# soldering_iron_2.net
KiCad netlist of a schematic drawn in Altium Designer
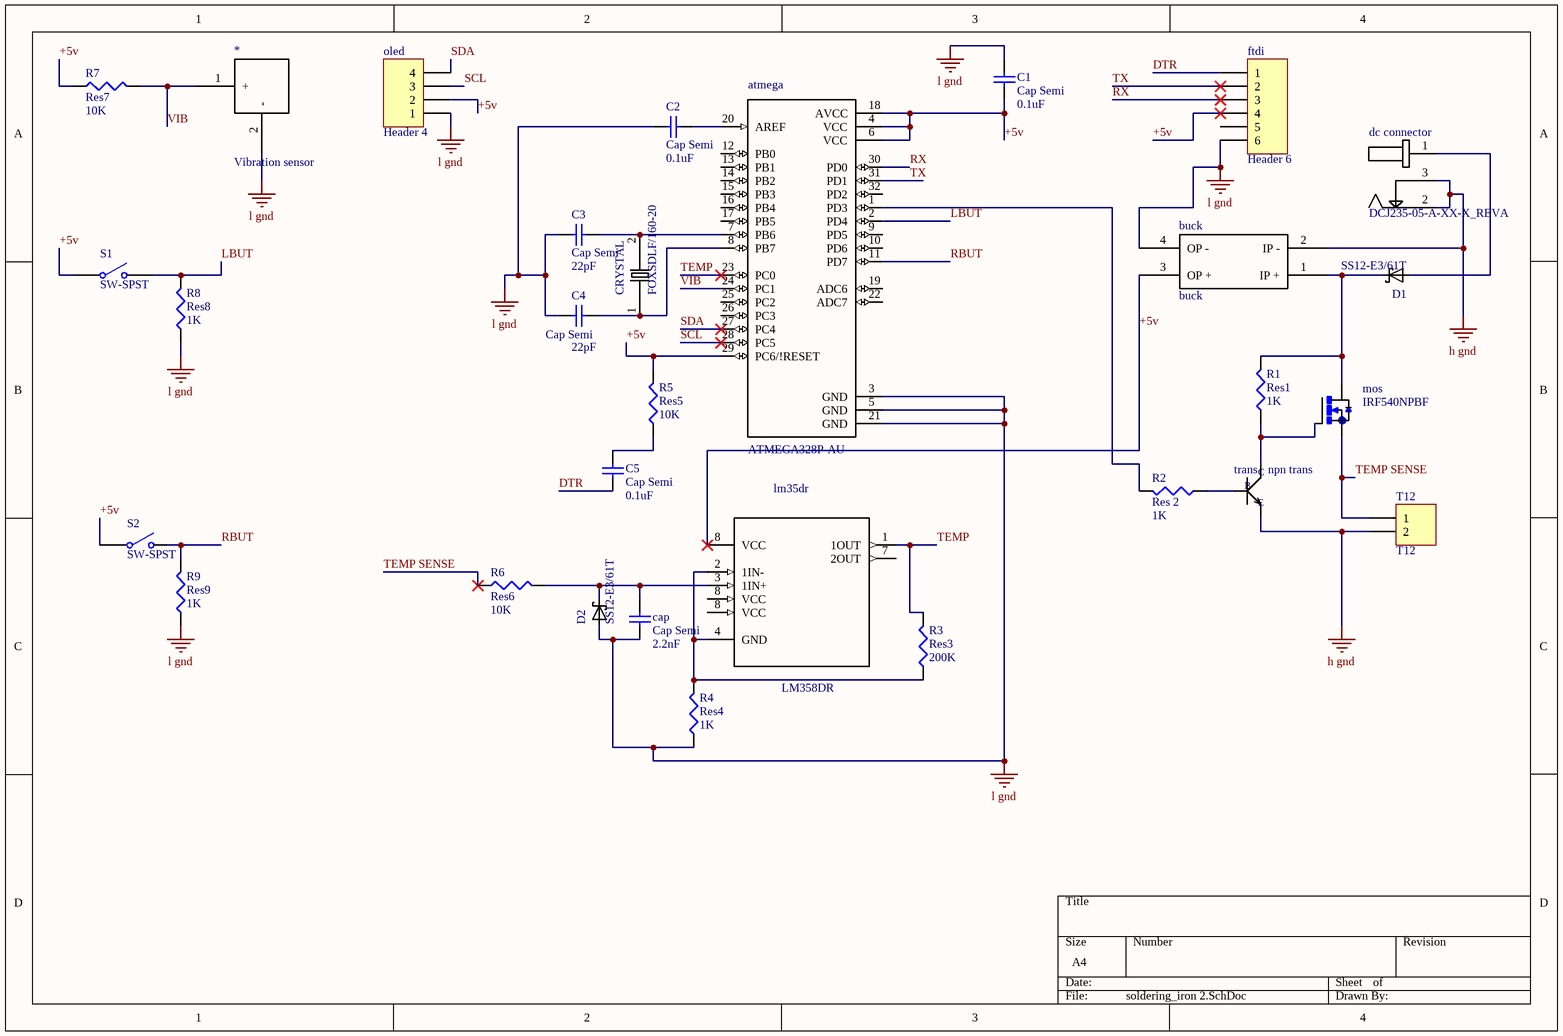
[diagram p0: soldering_iron 2.SchDoc]

(export (version "E")
  (design (tool "Eeschema 10.0.6"))
  (components
    (comp (ref "*")
      (value "Vibration sensor")
      (footprint "vibration sensor:PCBComponent_1")
      (libsource (lib "vibration sensor") (part "Component_1"))
    )
    (comp (ref "atmega")
      (value "ATMEGA328P-AU")
      (footprint "*QFP80P900X900X120-32N")
      (description "Microcontroller Mcu, 8 Bit, Atmega, 20mhz, Tqfp-32")
      (fields (field (name "DIGI-KEY_PART_NUMBER") "ATMEGA328P-AU-ND") (field (name "MF") "Microchip"))
      (libsource (lib "ATMEGA328P-AU") (part "ATMEGA328P-AU"))
    )
    (comp (ref "buck") (value "buck") (footprint "buck:buck") (libsource (lib "Schlib1") (part "buck")))
    (comp (ref "C1")
      (value "Cap Semi")
      (footprint "C1206")
      (description "Capacitor (Semiconductor SIM Model)")
      (fields (field (name "ALTIUM_VALUE") "0.1uF") (field (name "PUBLISHER") "Altium Limited"))
      (libsource (lib "Miscellaneous Devices") (part "Cap Semi"))
    )
    (comp (ref "C2")
      (value "Cap Semi")
      (footprint "C1206")
      (description "Capacitor (Semiconductor SIM Model)")
      (fields (field (name "ALTIUM_VALUE") "0.1uF") (field (name "PUBLISHER") "Altium Limited"))
      (libsource (lib "Miscellaneous Devices") (part "Cap Semi"))
    )
    (comp (ref "C3")
      (value "Cap Semi")
      (footprint "C1206")
      (description "Capacitor (Semiconductor SIM Model)")
      (fields (field (name "ALTIUM_VALUE") "22pF") (field (name "PUBLISHER") "Altium Limited"))
      (libsource (lib "Miscellaneous Devices") (part "Cap Semi"))
    )
    (comp (ref "C4")
      (value "Cap Semi")
      (footprint "C1206")
      (description "Capacitor (Semiconductor SIM Model)")
      (fields (field (name "ALTIUM_VALUE") "22pF") (field (name "PUBLISHER") "Altium Limited"))
      (libsource (lib "Miscellaneous Devices") (part "Cap Semi"))
    )
    (comp (ref "C5")
      (value "Cap Semi")
      (footprint "C1206")
      (description "Capacitor (Semiconductor SIM Model)")
      (fields (field (name "ALTIUM_VALUE") "0.1uF") (field (name "PUBLISHER") "Altium Limited"))
      (libsource (lib "Miscellaneous Devices") (part "Cap Semi"))
    )
    (comp (ref "cap")
      (value "Cap Semi")
      (footprint "C1206")
      (description "Capacitor (Semiconductor SIM Model)")
      (fields (field (name "ALTIUM_VALUE") "2.2nF") (field (name "PUBLISHER") "Altium Limited"))
      (libsource (lib "Miscellaneous Devices") (part "Cap Semi"))
    )
    (comp (ref "CRYSTAL")
      (value "FOXSDLF/160-20")
      (footprint "*XTAL_FOXSDLF/160-20")
      (description "Crystal 16MHz Â±30ppm _Tol_ Â±50ppm _Stability_ 20pF FUND 40Ohm 2-Pin HC-49/SDLF SMD T/R")
      (fields (field (name "MP") "FOXSDLF/160-20/TR") (field (name "MF") "Fox Electronics"))
      (libsource (lib "FOXSDLF_160-20") (part "FOXSDLF/160-20"))
    )
    (comp (ref "D1")
      (value "SS12-E3/61T")
      (footprint "*DO214AC_SS12-E3/61T(Primary)")
      (description "SS12 Series 20 V 1 A Surface Mount Schottky Barrier Rectifier - DO-214AC _SMA_")
      (fields (field (name "MF") "Vishay Semiconductor"))
      (libsource (lib "SS12-E3_61T") (part "SS12-E3/61T"))
    )
    (comp (ref "D2")
      (value "SS12-E3/61T")
      (footprint "*DO214AC_SS12-E3/61T(Primary)")
      (description "SS12 Series 20 V 1 A Surface Mount Schottky Barrier Rectifier - DO-214AC _SMA_")
      (fields (field (name "MF") "Vishay Semiconductor"))
      (libsource (lib "SS12-E3_61T") (part "SS12-E3/61T"))
    )
    (comp (ref "dc connector")
      (value "DCJ235-05-A-XX-X_REVA")
      (footprint "*GCT_DCJ235-05-A-XX-X_REVA")
      (description "Dc Power Jack, 5a, 20vdc, Black")
      (fields (field (name "MF") "Global Connector Technology") (field (name "MP") "DCJ235-05-A-K1-A"))
      (libsource (lib "DCJ235-05-A-XX-X_REVA") (part "DCJ235-05-A-XX-X_REVA"))
    )
    (comp (ref "ftdi")
      (value "Header 6")
      (footprint "HDR1X6")
      (description "Header, 6-Pin")
      (fields (field (name "PUBLISHER") "Altium Limited"))
      (libsource (lib "Miscellaneous Connectors") (part "Header 6"))
    )
    (comp (ref "lm35dr")
      (value "LM358DR")
      (footprint "*SOIC127P600X175-8N")
      (description "Dual Operational Amplifiers 8-SOIC 0 to 70")
      (fields (field (name "MF") "Texas Instruments"))
      (libsource (lib "LM358DR") (part "LM358DR"))
    )
    (comp (ref "mos")
      (value "IRF540NPBF")
      (footprint "*D2PACK")
      (description "Single N-Channel 100 V 44 mOhm 71 nC HEXFETÂ® Power Mosfet - TO-220-3")
      (fields (field (name "DIGI-KEY_PART_NUMBER") "IRF540NPBF-ND") (field (name "MF") "Infineon"))
      (libsource (lib "IRF540NPBF") (part "IRF540NPBF"))
    )
    (comp (ref "oled")
      (value "Header 4")
      (footprint "HDR1X4")
      (description "Header, 4-Pin")
      (fields (field (name "PUBLISHER") "Altium Limited"))
      (libsource (lib "Miscellaneous Connectors") (part "Header 4"))
    )
    (comp (ref "R1")
      (value "Res1")
      (footprint "J1-0603")
      (description "Resistor")
      (fields (field (name "ALTIUM_VALUE") "1K") (field (name "PUBLISHER") "Altium Limited"))
      (libsource (lib "Miscellaneous Devices") (part "Res3"))
    )
    (comp (ref "R2")
      (value "Res 2")
      (footprint "J1-0603")
      (description "Resistor")
      (fields (field (name "ALTIUM_VALUE") "1K") (field (name "PUBLISHER") "Altium Limited"))
      (libsource (lib "Miscellaneous Devices") (part "Res3"))
    )
    (comp (ref "R3")
      (value "Res3")
      (footprint "J1-0603")
      (description "Resistor")
      (fields (field (name "ALTIUM_VALUE") "200K") (field (name "PUBLISHER") "Altium Limited"))
      (libsource (lib "Miscellaneous Devices") (part "Res3"))
    )
    (comp (ref "R4")
      (value "Res4")
      (footprint "J1-0603")
      (description "Resistor")
      (fields (field (name "ALTIUM_VALUE") "1K") (field (name "PUBLISHER") "Altium Limited"))
      (libsource (lib "Miscellaneous Devices") (part "Res3"))
    )
    (comp (ref "R5")
      (value "Res5")
      (footprint "J1-0603")
      (description "Resistor")
      (fields (field (name "ALTIUM_VALUE") "10K") (field (name "PUBLISHER") "Altium Limited"))
      (libsource (lib "Miscellaneous Devices") (part "Res3"))
    )
    (comp (ref "R6")
      (value "Res6")
      (footprint "J1-0603")
      (description "Resistor")
      (fields (field (name "ALTIUM_VALUE") "10K") (field (name "PUBLISHER") "Altium Limited"))
      (libsource (lib "Miscellaneous Devices") (part "Res3"))
    )
    (comp (ref "R7")
      (value "Res7")
      (footprint "J1-0603")
      (description "Resistor")
      (fields (field (name "ALTIUM_VALUE") "10K") (field (name "PUBLISHER") "Altium Limited"))
      (libsource (lib "Miscellaneous Devices") (part "Res3"))
    )
    (comp (ref "R8")
      (value "Res8")
      (footprint "J1-0603")
      (description "Resistor")
      (fields (field (name "ALTIUM_VALUE") "1K") (field (name "PUBLISHER") "Altium Limited"))
      (libsource (lib "Miscellaneous Devices") (part "Res3"))
    )
    (comp (ref "R9")
      (value "Res9")
      (footprint "J1-0603")
      (description "Resistor")
      (fields (field (name "ALTIUM_VALUE") "1K") (field (name "PUBLISHER") "Altium Limited"))
      (libsource (lib "Miscellaneous Devices") (part "Res3"))
    )
    (comp (ref "S1")
      (value "SW-SPST")
      (footprint "SPST-2")
      (description "Single-Pole, Single-Throw Switch")
      (fields (field (name "PUBLISHER") "Altium Limited"))
      (libsource (lib "Miscellaneous Devices") (part "SW-SPST"))
    )
    (comp (ref "S2")
      (value "SW-SPST")
      (footprint "SPST-2")
      (description "Single-Pole, Single-Throw Switch")
      (fields (field (name "PUBLISHER") "Altium Limited"))
      (libsource (lib "Miscellaneous Devices") (part "SW-SPST"))
    )
    (comp (ref "T12")
      (value "T12")
      (footprint "HDR1X2")
      (description "Header, 2-Pin")
      (fields (field (name "PUBLISHER") "Altium Limited"))
      (libsource (lib "Miscellaneous Connectors") (part "Header 2"))
    )
    (comp (ref "trans")
      (value "npn trans")
      (footprint "*SOT-23")
      (description "SMD Transistors NPN 25V-500mA")
      (fields (field (name "MP") "S9013") (field (name "MF") "JCET"))
      (libsource (lib "SMD-TRANSISTORS-NPN-25V-500MA-S9013_SOT-23_") (part "SMD-TRANSISTORS-NPN-25V-500MA-S9013(SOT-23)"))
    )
  )
  (nets
    (net (code "1") (name "/+5v") (class "Default")
      (node (ref "C1") (pin "1") (pinfunction "1_1") (pintype "passive"))
      (node (ref "R5") (pin "2") (pinfunction "2_2") (pintype "passive"))
      (node (ref "R7") (pin "1") (pinfunction "1_1") (pintype "passive"))
      (node (ref "S1") (pin "1") (pinfunction "COMMON_1") (pintype "passive"))
      (node (ref "S2") (pin "1") (pinfunction "COMMON_1") (pintype "passive"))
      (node (ref "atmega") (pin "18") (pinfunction "AVCC_18") (pintype "power_in"))
      (node (ref "atmega") (pin "29") (pinfunction "PC6/!RESET_29") (pintype "bidirectional"))
      (node (ref "atmega") (pin "4") (pinfunction "VCC_4") (pintype "power_in"))
      (node (ref "atmega") (pin "6") (pinfunction "VCC_6") (pintype "power_in"))
      (node (ref "buck") (pin "3") (pinfunction "OP_+_3") (pintype "passive"))
      (node (ref "ftdi") (pin "4") (pinfunction "4_4") (pintype "passive"))
      (node (ref "lm35dr") (pin "8") (pinfunction "VCC_8") (pintype "power_in"))
      (node (ref "oled") (pin "2") (pinfunction "2_2") (pintype "passive"))
    )
    (net (code "2") (name "/DTR") (class "Default")
      (node (ref "C5") (pin "1") (pinfunction "1_1") (pintype "passive"))
      (node (ref "ftdi") (pin "1") (pinfunction "1_1") (pintype "passive"))
    )
    (net (code "3") (name "/LBUT") (class "Default")
      (node (ref "R8") (pin "2") (pinfunction "2_2") (pintype "passive"))
      (node (ref "S1") (pin "2") (pinfunction "NO_2") (pintype "passive"))
      (node (ref "atmega") (pin "2") (pinfunction "PD4_2") (pintype "bidirectional"))
    )
    (net (code "4") (name "/RBUT") (class "Default")
      (node (ref "R9") (pin "2") (pinfunction "2_2") (pintype "passive"))
      (node (ref "S2") (pin "2") (pinfunction "NO_2") (pintype "passive"))
      (node (ref "atmega") (pin "11") (pinfunction "PD7_11") (pintype "bidirectional"))
    )
    (net (code "5") (name "/RX") (class "Default")
      (node (ref "atmega") (pin "30") (pinfunction "PD0_30") (pintype "bidirectional"))
      (node (ref "ftdi") (pin "3") (pinfunction "3_3") (pintype "passive"))
    )
    (net (code "6") (name "/SCL") (class "Default")
      (node (ref "atmega") (pin "28") (pinfunction "PC5_28") (pintype "bidirectional"))
      (node (ref "oled") (pin "3") (pinfunction "3_3") (pintype "passive"))
    )
    (net (code "7") (name "/SDA") (class "Default")
      (node (ref "atmega") (pin "27") (pinfunction "PC4_27") (pintype "bidirectional"))
      (node (ref "oled") (pin "4") (pinfunction "4_4") (pintype "passive"))
    )
    (net (code "8") (name "/TEMP") (class "Default")
      (node (ref "R3") (pin "2") (pinfunction "2_2") (pintype "passive"))
      (node (ref "atmega") (pin "23") (pinfunction "PC0_23") (pintype "bidirectional"))
      (node (ref "lm35dr") (pin "1") (pinfunction "1OUT_1") (pintype "output"))
    )
    (net (code "9") (name "/TEMP SENSE") (class "Default")
      (node (ref "R6") (pin "1") (pinfunction "1_1") (pintype "passive"))
      (node (ref "T12") (pin "1") (pinfunction "1_1") (pintype "passive"))
      (node (ref "mos") (pin "3") (pinfunction "S_3") (pintype "passive"))
    )
    (net (code "10") (name "/TX") (class "Default")
      (node (ref "atmega") (pin "31") (pinfunction "PD1_31") (pintype "bidirectional"))
      (node (ref "ftdi") (pin "2") (pinfunction "2_2") (pintype "passive"))
    )
    (net (code "11") (name "/VIB") (class "Default")
      (node (ref "*") (pin "1") (pinfunction "+_1") (pintype "passive"))
      (node (ref "R7") (pin "2") (pinfunction "2_2") (pintype "passive"))
      (node (ref "atmega") (pin "24") (pinfunction "PC1_24") (pintype "bidirectional"))
    )
    (net (code "12") (name "Net-(C5-Pad2)") (class "Default")
      (node (ref "C5") (pin "2") (pinfunction "2_2") (pintype "passive"))
      (node (ref "R5") (pin "1") (pinfunction "1_1") (pintype "passive"))
    )
    (net (code "13") (name "Net-(D1-PadA)") (class "Default")
      (node (ref "D1") (pin "A") (pinfunction "A_A") (pintype "passive"))
      (node (ref "dc connector") (pin "1") (pinfunction "1_1") (pintype "passive"))
    )
    (net (code "14") (name "Net-(atmega-AREF)") (class "Default")
      (node (ref "C2") (pin "2") (pinfunction "2_2") (pintype "passive"))
      (node (ref "atmega") (pin "20") (pinfunction "AREF_20") (pintype "input"))
    )
    (net (code "15") (name "Net-(atmega-PB6)") (class "Default")
      (node (ref "C3") (pin "2") (pinfunction "2_2") (pintype "passive"))
      (node (ref "CRYSTAL") (pin "2") (pinfunction "2_2") (pintype "passive"))
      (node (ref "atmega") (pin "7") (pinfunction "PB6_7") (pintype "bidirectional"))
    )
    (net (code "16") (name "Net-(atmega-PB7)") (class "Default")
      (node (ref "C4") (pin "2") (pinfunction "2_2") (pintype "passive"))
      (node (ref "CRYSTAL") (pin "1") (pinfunction "1_1") (pintype "passive"))
      (node (ref "atmega") (pin "8") (pinfunction "PB7_8") (pintype "bidirectional"))
    )
    (net (code "17") (name "Net-(atmega-PD3)") (class "Default")
      (node (ref "R2") (pin "2") (pinfunction "2_2") (pintype "passive"))
      (node (ref "atmega") (pin "1") (pinfunction "PD3_1") (pintype "bidirectional"))
    )
    (net (code "18") (name "Net-(buck-IP_+)") (class "Default")
      (node (ref "D1") (pin "C") (pinfunction "C_C") (pintype "passive"))
      (node (ref "R1") (pin "2") (pinfunction "2_2") (pintype "passive"))
      (node (ref "buck") (pin "1") (pinfunction "IP_+_1") (pintype "passive"))
      (node (ref "mos") (pin "2") (pinfunction "D_2") (pintype "passive"))
    )
    (net (code "19") (name "Net-(lm35dr-1IN+)") (class "Default")
      (node (ref "D2") (pin "C") (pinfunction "C_C") (pintype "passive"))
      (node (ref "R6") (pin "2") (pinfunction "2_2") (pintype "passive"))
      (node (ref "cap") (pin "2") (pinfunction "2_2") (pintype "passive"))
      (node (ref "lm35dr") (pin "3") (pinfunction "1IN+_3") (pintype "input"))
    )
    (net (code "20") (name "Net-(lm35dr-1IN-)") (class "Default")
      (node (ref "R3") (pin "1") (pinfunction "1_1") (pintype "passive"))
      (node (ref "R4") (pin "2") (pinfunction "2_2") (pintype "passive"))
      (node (ref "lm35dr") (pin "2") (pinfunction "1IN-_2") (pintype "input"))
      (node (ref "lm35dr") (pin "4") (pinfunction "GND_4") (pintype "passive"))
    )
    (net (code "21") (name "Net-(mos-G)") (class "Default")
      (node (ref "R1") (pin "1") (pinfunction "1_1") (pintype "passive"))
      (node (ref "mos") (pin "1") (pinfunction "G_1") (pintype "passive"))
      (node (ref "trans") (pin "3") (pinfunction "C_3") (pintype "passive"))
    )
    (net (code "22") (name "Net-(trans-B)") (class "Default")
      (node (ref "R2") (pin "1") (pinfunction "1_1") (pintype "passive"))
      (node (ref "trans") (pin "1") (pinfunction "B_1") (pintype "passive"))
    )
    (net (code "23") (name "h gnd") (class "Default")
      (node (ref "T12") (pin "2") (pinfunction "2_2") (pintype "passive"))
      (node (ref "buck") (pin "2") (pinfunction "IP_-_2") (pintype "passive"))
      (node (ref "dc connector") (pin "2") (pinfunction "2_2") (pintype "passive"))
      (node (ref "dc connector") (pin "3") (pinfunction "3_3") (pintype "passive"))
      (node (ref "trans") (pin "2") (pinfunction "E_2") (pintype "passive"))
    )
    (net (code "24") (name "l gnd") (class "Default")
      (node (ref "*") (pin "2") (pinfunction "-_2") (pintype "passive"))
      (node (ref "C1") (pin "2") (pinfunction "2_2") (pintype "passive"))
      (node (ref "C2") (pin "1") (pinfunction "1_1") (pintype "passive"))
      (node (ref "C3") (pin "1") (pinfunction "1_1") (pintype "passive"))
      (node (ref "C4") (pin "1") (pinfunction "1_1") (pintype "passive"))
      (node (ref "D2") (pin "A") (pinfunction "A_A") (pintype "passive"))
      (node (ref "R4") (pin "1") (pinfunction "1_1") (pintype "passive"))
      (node (ref "R8") (pin "1") (pinfunction "1_1") (pintype "passive"))
      (node (ref "R9") (pin "1") (pinfunction "1_1") (pintype "passive"))
      (node (ref "atmega") (pin "21") (pinfunction "GND_21") (pintype "power_in"))
      (node (ref "atmega") (pin "3") (pinfunction "GND_3") (pintype "power_in"))
      (node (ref "atmega") (pin "5") (pinfunction "GND_5") (pintype "power_in"))
      (node (ref "buck") (pin "4") (pinfunction "OP_-_4") (pintype "passive"))
      (node (ref "cap") (pin "1") (pinfunction "1_1") (pintype "passive"))
      (node (ref "ftdi") (pin "6") (pinfunction "6_6") (pintype "passive"))
      (node (ref "oled") (pin "1") (pinfunction "1_1") (pintype "passive"))
    )
    (net (code "25") (name "unconnected-(atmega-ADC6-Pad19)") (class "Default")
      (node (ref "atmega") (pin "19") (pinfunction "ADC6_19") (pintype "bidirectional"))
    )
    (net (code "26") (name "unconnected-(atmega-ADC7-Pad22)") (class "Default")
      (node (ref "atmega") (pin "22") (pinfunction "ADC7_22") (pintype "bidirectional"))
    )
    (net (code "27") (name "unconnected-(atmega-PB0-Pad12)") (class "Default")
      (node (ref "atmega") (pin "12") (pinfunction "PB0_12") (pintype "bidirectional"))
    )
    (net (code "28") (name "unconnected-(atmega-PB1-Pad13)") (class "Default")
      (node (ref "atmega") (pin "13") (pinfunction "PB1_13") (pintype "bidirectional"))
    )
    (net (code "29") (name "unconnected-(atmega-PB2-Pad14)") (class "Default")
      (node (ref "atmega") (pin "14") (pinfunction "PB2_14") (pintype "bidirectional"))
    )
    (net (code "30") (name "unconnected-(atmega-PB3-Pad15)") (class "Default")
      (node (ref "atmega") (pin "15") (pinfunction "PB3_15") (pintype "bidirectional"))
    )
    (net (code "31") (name "unconnected-(atmega-PB4-Pad16)") (class "Default")
      (node (ref "atmega") (pin "16") (pinfunction "PB4_16") (pintype "bidirectional"))
    )
    (net (code "32") (name "unconnected-(atmega-PB5-Pad17)") (class "Default")
      (node (ref "atmega") (pin "17") (pinfunction "PB5_17") (pintype "bidirectional"))
    )
    (net (code "33") (name "unconnected-(atmega-PC2-Pad25)") (class "Default")
      (node (ref "atmega") (pin "25") (pinfunction "PC2_25") (pintype "bidirectional"))
    )
    (net (code "34") (name "unconnected-(atmega-PC3-Pad26)") (class "Default")
      (node (ref "atmega") (pin "26") (pinfunction "PC3_26") (pintype "bidirectional"))
    )
    (net (code "35") (name "unconnected-(atmega-PD2-Pad32)") (class "Default")
      (node (ref "atmega") (pin "32") (pinfunction "PD2_32") (pintype "bidirectional"))
    )
    (net (code "36") (name "unconnected-(atmega-PD5-Pad9)") (class "Default")
      (node (ref "atmega") (pin "9") (pinfunction "PD5_9") (pintype "bidirectional"))
    )
    (net (code "37") (name "unconnected-(atmega-PD6-Pad10)") (class "Default")
      (node (ref "atmega") (pin "10") (pinfunction "PD6_10") (pintype "bidirectional"))
    )
    (net (code "38") (name "unconnected-(ftdi-Pad5)") (class "Default")
      (node (ref "ftdi") (pin "5") (pinfunction "5_5") (pintype "passive"))
    )
    (net (code "39") (name "unconnected-(lm35dr-2OUT-Pad7)") (class "Default")
      (node (ref "lm35dr") (pin "7") (pinfunction "2OUT_7") (pintype "output"))
    )
    (net (code "40") (name "unconnected-(lm35dr-VCC-Pad8)") (class "Default")
      (node (ref "lm35dr") (pin "8") (pinfunction "VCC_8") (pintype "input"))
    )
    (net (code "41") (name "unconnected-(lm35dr-VCC-Pad8)_1") (class "Default")
      (node (ref "lm35dr") (pin "8") (pinfunction "VCC_8") (pintype "input"))
    )
  )
)
